# IRN-back-RCA.net
KiCad netlist of a schematic drawn in Altium Designer
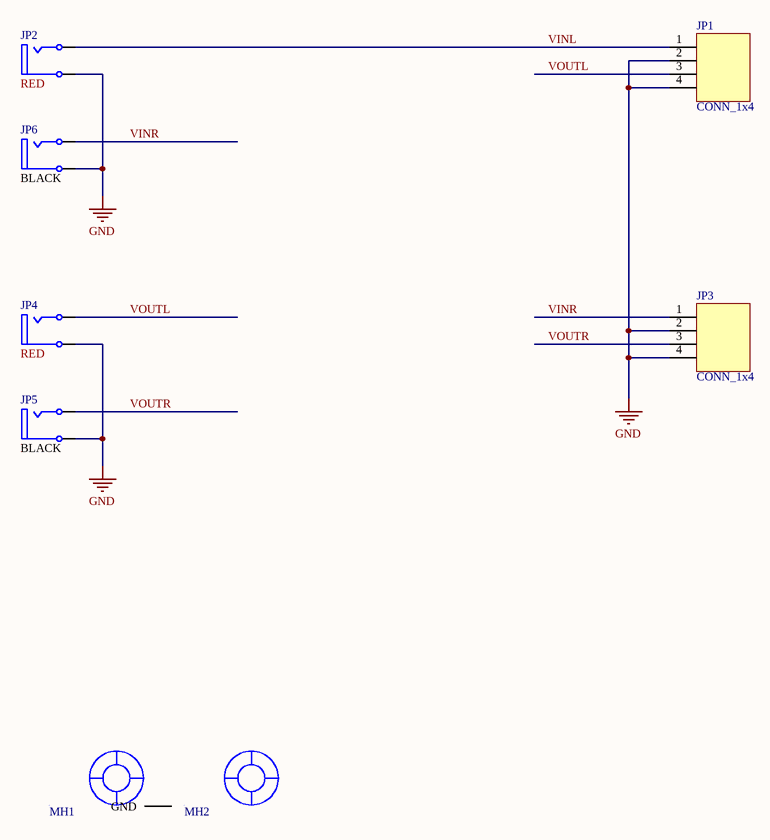
[diagram p0: IRN-back-RCA.SchDoc]

(export (version "E")
  (design (tool "Eeschema 10.0.6"))
  (components
    (comp (ref "JP1")
      (value "CONN_1x4")
      (footprint "CONN_HDR1X4-No3D")
      (description "Header, 4-Pin")
      (fields (field (name "MPN") "0470531000") (field (name "PUBLISHER") "Altium Limited"))
      (libsource (lib "micun") (part "CONN_MHDR_1x4"))
    )
    (comp (ref "JP2")
      (value "RED")
      (footprint "CONN_RCA-Lumberg-BTOR")
      (description "RCA panel-mount socket red, 1553 02 rot, Lumberg Connect GmbH")
      (fields (field (name "MPN") "BTOR 1 ROT") (field (name "Comment") "RCA RED"))
      (libsource (lib "micun") (part "CONN_RCA_LUMBERG_BTOR_1_RED"))
    )
    (comp (ref "JP3")
      (value "CONN_1x4")
      (footprint "CONN_HDR1X4-No3D")
      (description "Header, 4-Pin")
      (fields (field (name "MPN") "0470531000") (field (name "PUBLISHER") "Altium Limited"))
      (libsource (lib "micun") (part "CONN_MHDR_1x4"))
    )
    (comp (ref "JP4")
      (value "RED")
      (footprint "CONN_RCA-Lumberg-BTOR")
      (description "RCA panel-mount socket red, 1553 02 rot, Lumberg Connect GmbH")
      (fields (field (name "MPN") "BTOR 1 ROT") (field (name "Comment") "RCA RED"))
      (libsource (lib "micun") (part "CONN_RCA_LUMBERG_BTOR_1_RED"))
    )
    (comp (ref "JP5")
      (value "BLACK")
      (footprint "CONN_RCA-Lumberg-BTOR")
      (description "RCA panel-mount socket red, 1553 02 rot, Lumberg Connect GmbH")
      (fields (field (name "MPN") "BTOR 1 SCHWARZ") (field (name "Comment") "RCA BLACK"))
      (libsource (lib "micun") (part "CONN_RCA_LUMBERG_BTOR_1_BLACK"))
    )
    (comp (ref "JP6")
      (value "BLACK")
      (footprint "CONN_RCA-Lumberg-BTOR")
      (description "RCA panel-mount socket red, 1553 02 rot, Lumberg Connect GmbH")
      (fields (field (name "MPN") "BTOR 1 SCHWARZ") (field (name "Comment") "RCA BLACK"))
      (libsource (lib "micun") (part "CONN_RCA_LUMBERG_BTOR_1_BLACK"))
    )
    (comp (ref "MH1")
      (value "Mounting hole")
      (footprint "MECH_MHOLE_3.5-GND")
      (libsource (lib "micun") (part "MECH_MHOLE"))
    )
    (comp (ref "MH2")
      (value "Mounting hole")
      (footprint "MECH_MHOLE_3.5")
      (libsource (lib "") (part "MECH_MHOLE_1"))
    )
  )
  (nets
    (net (code "1") (name "/VINL") (class "Default")
      (node (ref "JP1") (pin "1") (pinfunction "1_1") (pintype "passive"))
      (node (ref "JP2") (pin "1") (pinfunction "Signal_1") (pintype "passive"))
    )
    (net (code "2") (name "/VINR") (class "Default")
      (node (ref "JP3") (pin "1") (pinfunction "1_1") (pintype "passive"))
      (node (ref "JP6") (pin "1") (pinfunction "Signal_1") (pintype "passive"))
    )
    (net (code "3") (name "/VOUTL") (class "Default")
      (node (ref "JP1") (pin "3") (pinfunction "3_3") (pintype "passive"))
      (node (ref "JP4") (pin "1") (pinfunction "Signal_1") (pintype "passive"))
    )
    (net (code "4") (name "/VOUTR") (class "Default")
      (node (ref "JP3") (pin "3") (pinfunction "3_3") (pintype "passive"))
      (node (ref "JP5") (pin "1") (pinfunction "Signal_1") (pintype "passive"))
    )
    (net (code "5") (name "GND") (class "Default")
      (node (ref "JP1") (pin "2") (pinfunction "2_2") (pintype "passive"))
      (node (ref "JP1") (pin "4") (pinfunction "4_4") (pintype "passive"))
      (node (ref "JP2") (pin "2") (pinfunction "Ground_2") (pintype "power_in"))
      (node (ref "JP3") (pin "2") (pinfunction "2_2") (pintype "passive"))
      (node (ref "JP3") (pin "4") (pinfunction "4_4") (pintype "passive"))
      (node (ref "JP4") (pin "2") (pinfunction "Ground_2") (pintype "power_in"))
      (node (ref "JP5") (pin "2") (pinfunction "Ground_2") (pintype "power_in"))
      (node (ref "JP6") (pin "2") (pinfunction "Ground_2") (pintype "power_in"))
    )
    (net (code "6") (name "unconnected-(MH1-GND-Pad0)") (class "Default")
      (node (ref "MH1") (pin "0") (pinfunction "GND_0") (pintype "power_in"))
    )
  )
)
